# 009_ToSourceBoard.net
KiCad netlist of a schematic drawn in Altium Designer
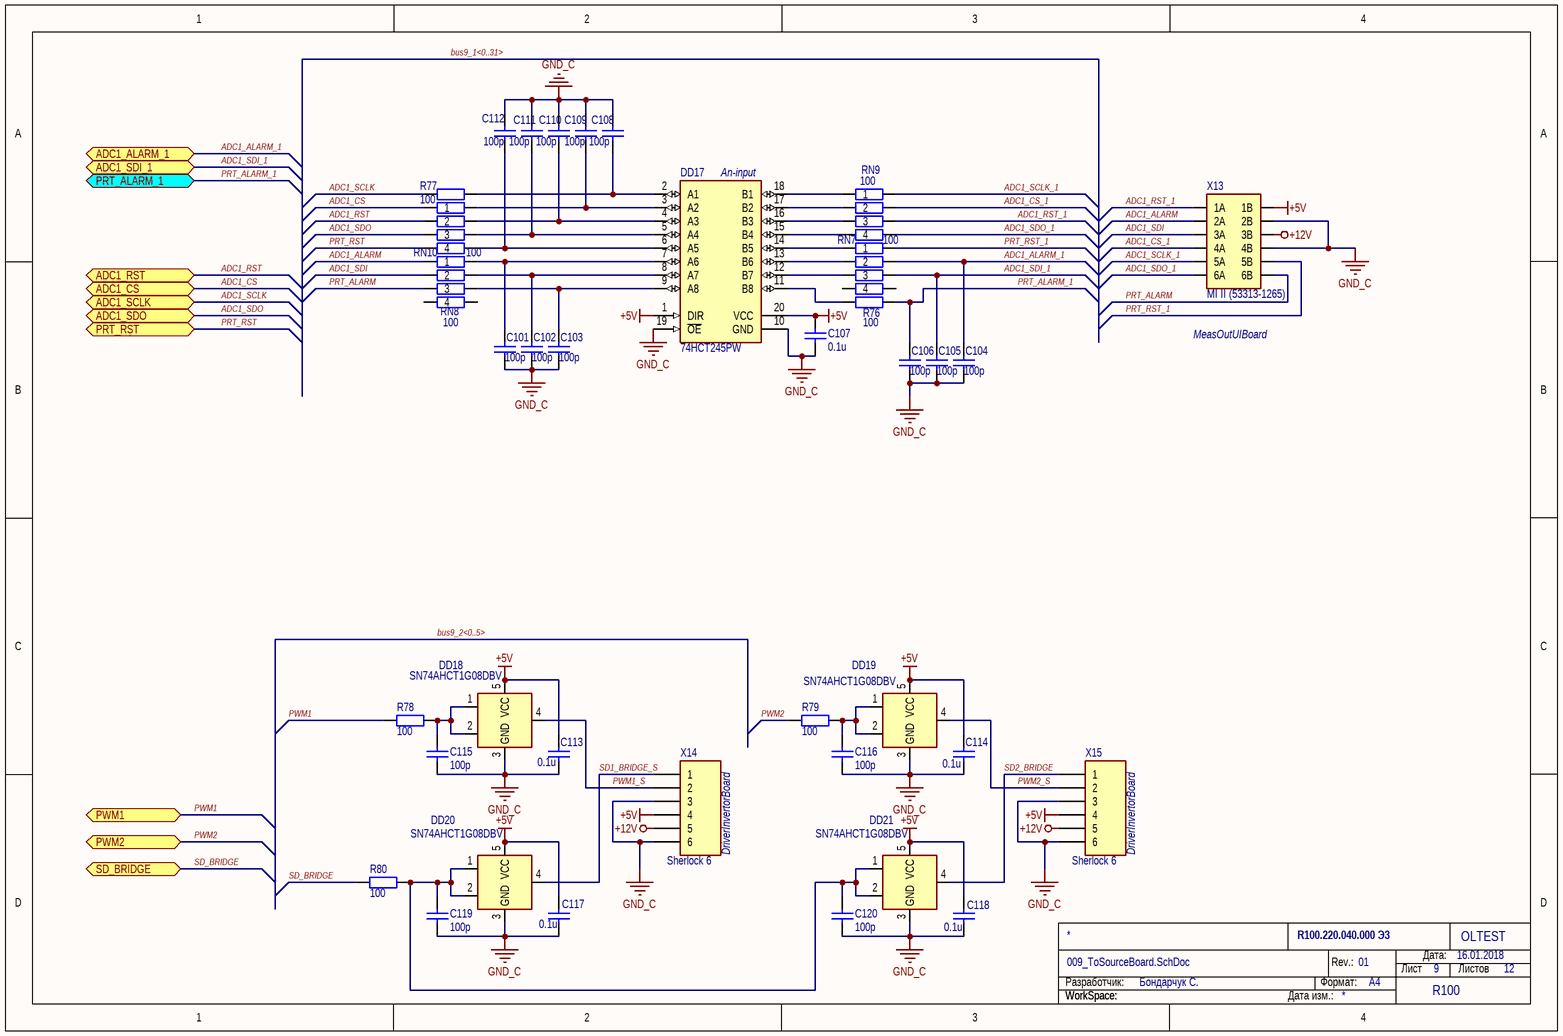
[diagram p0: 009_ToSourceBoard.SchDoc]

(export (version "E")
  (design (tool "Eeschema 10.0.6"))
  (components
    (comp (ref "C101")
      (value "100p")
      (footprint "mainLib:SMD_C_0603")
      (description "SMD C 0603 MURATA 100V 5% NP0")
      (fields (field (name "PARTNUMBER") "GRM1885C2A101JA01") (field (name "MANUFACTURER") "MURATA"))
      (libsource (lib "mainRCLib") (part "C0603 100p 100V 5%"))
    )
    (comp (ref "C102")
      (value "100p")
      (footprint "mainLib:SMD_C_0603")
      (description "SMD C 0603 MURATA 100V 5% NP0")
      (fields (field (name "PARTNUMBER") "GRM1885C2A101JA01") (field (name "MANUFACTURER") "MURATA"))
      (libsource (lib "mainRCLib") (part "C0603 100p 100V 5%"))
    )
    (comp (ref "C103")
      (value "100p")
      (footprint "mainLib:SMD_C_0603")
      (description "SMD C 0603 MURATA 100V 5% NP0")
      (fields (field (name "PARTNUMBER") "GRM1885C2A101JA01") (field (name "MANUFACTURER") "MURATA"))
      (libsource (lib "mainRCLib") (part "C0603 100p 100V 5%"))
    )
    (comp (ref "C104")
      (value "100p")
      (footprint "mainLib:SMD_C_0603")
      (description "SMD C 0603 MURATA 100V 5% NP0")
      (fields (field (name "PARTNUMBER") "GRM1885C2A101JA01") (field (name "MANUFACTURER") "MURATA"))
      (libsource (lib "mainRCLib") (part "C0603 100p 100V 5%"))
    )
    (comp (ref "C105")
      (value "100p")
      (footprint "mainLib:SMD_C_0603")
      (description "SMD C 0603 MURATA 100V 5% NP0")
      (fields (field (name "PARTNUMBER") "GRM1885C2A101JA01") (field (name "MANUFACTURER") "MURATA"))
      (libsource (lib "mainRCLib") (part "C0603 100p 100V 5%"))
    )
    (comp (ref "C106")
      (value "100p")
      (footprint "mainLib:SMD_C_0603")
      (description "SMD C 0603 MURATA 100V 5% NP0")
      (fields (field (name "PARTNUMBER") "GRM1885C2A101JA01") (field (name "MANUFACTURER") "MURATA"))
      (libsource (lib "mainRCLib") (part "C0603 100p 100V 5%"))
    )
    (comp (ref "C107")
      (value "0.1u")
      (footprint "mainLib:SMD_C_0603")
      (description "SMD C 0603 MURATA 50V 10% X7R")
      (fields (field (name "PARTNUMBER") "GRM188R71H104K") (field (name "MANUFACTURER") "MURATA"))
      (libsource (lib "mainRCLib") (part "C0603 0.1u 50V 10%"))
    )
    (comp (ref "C108")
      (value "100p")
      (footprint "mainLib:SMD_C_0603")
      (description "SMD C 0603 MURATA 100V 5% NP0")
      (fields (field (name "PARTNUMBER") "GRM1885C2A101JA01") (field (name "MANUFACTURER") "MURATA"))
      (libsource (lib "mainRCLib") (part "C0603 100p 100V 5%"))
    )
    (comp (ref "C109")
      (value "100p")
      (footprint "mainLib:SMD_C_0603")
      (description "SMD C 0603 MURATA 100V 5% NP0")
      (fields (field (name "PARTNUMBER") "GRM1885C2A101JA01") (field (name "MANUFACTURER") "MURATA"))
      (libsource (lib "mainRCLib") (part "C0603 100p 100V 5%"))
    )
    (comp (ref "C110")
      (value "100p")
      (footprint "mainLib:SMD_C_0603")
      (description "SMD C 0603 MURATA 100V 5% NP0")
      (fields (field (name "PARTNUMBER") "GRM1885C2A101JA01") (field (name "MANUFACTURER") "MURATA"))
      (libsource (lib "mainRCLib") (part "C0603 100p 100V 5%"))
    )
    (comp (ref "C111")
      (value "100p")
      (footprint "mainLib:SMD_C_0603")
      (description "SMD C 0603 MURATA 100V 5% NP0")
      (fields (field (name "PARTNUMBER") "GRM1885C2A101JA01") (field (name "MANUFACTURER") "MURATA"))
      (libsource (lib "mainRCLib") (part "C0603 100p 100V 5%"))
    )
    (comp (ref "C112")
      (value "100p")
      (footprint "mainLib:SMD_C_0603")
      (description "SMD C 0603 MURATA 100V 5% NP0")
      (fields (field (name "PARTNUMBER") "GRM1885C2A101JA01") (field (name "MANUFACTURER") "MURATA"))
      (libsource (lib "mainRCLib") (part "C0603 100p 100V 5%"))
    )
    (comp (ref "C113")
      (value "0.1u")
      (footprint "mainLib:SMD_C_0603")
      (description "SMD C 0603 MURATA 50V 10% X7R")
      (fields (field (name "PARTNUMBER") "GRM188R71H104K") (field (name "MANUFACTURER") "MURATA"))
      (libsource (lib "mainRCLib") (part "C0603 0.1u 50V 10%"))
    )
    (comp (ref "C114")
      (value "0.1u")
      (footprint "mainLib:SMD_C_0603")
      (description "SMD C 0603 MURATA 50V 10% X7R")
      (fields (field (name "PARTNUMBER") "GRM188R71H104K") (field (name "MANUFACTURER") "MURATA"))
      (libsource (lib "mainRCLib") (part "C0603 0.1u 50V 10%"))
    )
    (comp (ref "C115")
      (value "100p")
      (footprint "mainLib:SMD_C_0603")
      (description "SMD C 0603 MURATA 100V 5% NP0")
      (fields (field (name "PARTNUMBER") "GRM1885C2A101JA01") (field (name "MANUFACTURER") "MURATA"))
      (libsource (lib "mainRCLib") (part "C0603 100p 100V 5%"))
    )
    (comp (ref "C116")
      (value "100p")
      (footprint "mainLib:SMD_C_0603")
      (description "SMD C 0603 MURATA 100V 5% NP0")
      (fields (field (name "PARTNUMBER") "GRM1885C2A101JA01") (field (name "MANUFACTURER") "MURATA"))
      (libsource (lib "mainRCLib") (part "C0603 100p 100V 5%"))
    )
    (comp (ref "C117")
      (value "0.1u")
      (footprint "mainLib:SMD_C_0603")
      (description "SMD C 0603 MURATA 50V 10% X7R")
      (fields (field (name "PARTNUMBER") "GRM188R71H104K") (field (name "MANUFACTURER") "MURATA"))
      (libsource (lib "mainRCLib") (part "C0603 0.1u 50V 10%"))
    )
    (comp (ref "C118")
      (value "0.1u")
      (footprint "mainLib:SMD_C_0603")
      (description "SMD C 0603 MURATA 50V 10% X7R")
      (fields (field (name "PARTNUMBER") "GRM188R71H104K") (field (name "MANUFACTURER") "MURATA"))
      (libsource (lib "mainRCLib") (part "C0603 0.1u 50V 10%"))
    )
    (comp (ref "C119")
      (value "100p")
      (footprint "mainLib:SMD_C_0603")
      (description "SMD C 0603 MURATA 100V 5% NP0")
      (fields (field (name "PARTNUMBER") "GRM1885C2A101JA01") (field (name "MANUFACTURER") "MURATA"))
      (libsource (lib "mainRCLib") (part "C0603 100p 100V 5%"))
    )
    (comp (ref "C120")
      (value "100p")
      (footprint "mainLib:SMD_C_0603")
      (description "SMD C 0603 MURATA 100V 5% NP0")
      (fields (field (name "PARTNUMBER") "GRM1885C2A101JA01") (field (name "MANUFACTURER") "MURATA"))
      (libsource (lib "mainRCLib") (part "C0603 100p 100V 5%"))
    )
    (comp (ref "DD17")
      (value "74HCT245PW")
      (footprint "mainLib:PW0020A_M")
      (description "Octal Bus Transceivers With 3-State Outputs, PW0020A")
      (fields (field (name "MANUFACTURER") "NXP"))
      (libsource (lib "mainLib") (part "74HCT245PW"))
    )
    (comp (ref "DD18")
      (value "SN74AHCT1G08DBV")
      (footprint "mainLib:SOT-23(DBV)")
      (description "2-in AND")
      (fields (field (name "MANUFACTURER") "Texas Instruments"))
      (libsource (lib "mainLib") (part "SN74AHCT1G08DBV"))
    )
    (comp (ref "DD19")
      (value "SN74AHCT1G08DBV")
      (footprint "mainLib:SOT-23(DBV)")
      (description "2-in AND")
      (fields (field (name "MANUFACTURER") "Texas Instruments"))
      (libsource (lib "mainLib") (part "SN74AHCT1G08DBV"))
    )
    (comp (ref "DD20")
      (value "SN74AHCT1G08DBV")
      (footprint "mainLib:SOT-23(DBV)")
      (description "2-in AND")
      (fields (field (name "MANUFACTURER") "Texas Instruments"))
      (libsource (lib "mainLib") (part "SN74AHCT1G08DBV"))
    )
    (comp (ref "DD21")
      (value "SN74AHCT1G08DBV")
      (footprint "mainLib:SOT-23(DBV)")
      (description "2-in AND")
      (fields (field (name "MANUFACTURER") "Texas Instruments"))
      (libsource (lib "mainLib") (part "SN74AHCT1G08DBV"))
    )
    (comp (ref "R76")
      (value "100")
      (footprint "SMD_R_0603")
      (description "SMD R 0603 VISHAY 0.1W 75V 1% 100ppm")
      (fields (field (name "PARTNUMBER") "CRCW0603100RFK") (field (name "MANUFACTURER") "VISHAY"))
      (libsource (lib "mainRCLib") (part "R0603 100 1%"))
    )
    (comp (ref "R77")
      (value "100")
      (footprint "SMD_R_0603")
      (description "SMD R 0603 VISHAY 0.1W 75V 1% 100ppm")
      (fields (field (name "PARTNUMBER") "CRCW0603100RFK") (field (name "MANUFACTURER") "VISHAY"))
      (libsource (lib "mainRCLib") (part "R0603 100 1%"))
    )
    (comp (ref "R78")
      (value "100")
      (footprint "SMD_R_0603")
      (description "SMD R 0603 VISHAY 0.1W 75V 1% 100ppm")
      (fields (field (name "PARTNUMBER") "CRCW0603100RFK") (field (name "MANUFACTURER") "VISHAY"))
      (libsource (lib "mainRCLib") (part "R0603 100 1%"))
    )
    (comp (ref "R79")
      (value "100")
      (footprint "SMD_R_0603")
      (description "SMD R 0603 VISHAY 0.1W 75V 1% 100ppm")
      (fields (field (name "PARTNUMBER") "CRCW0603100RFK") (field (name "MANUFACTURER") "VISHAY"))
      (libsource (lib "mainRCLib") (part "R0603 100 1%"))
    )
    (comp (ref "R80")
      (value "100")
      (footprint "SMD_R_0603")
      (description "SMD R 0603 VISHAY 0.1W 75V 1% 100ppm")
      (fields (field (name "PARTNUMBER") "CRCW0603100RFK") (field (name "MANUFACTURER") "VISHAY"))
      (libsource (lib "mainRCLib") (part "R0603 100 1%"))
    )
    (comp (ref "RN7")
      (value "100")
      (footprint "mainLib:CRA06S")
      (description "SMD RESISTOR ARRAY VISHAY 0.063W 50V 1% 100ppm")
      (fields (field (name "PARTNUMBER") "CRA06S083100RF") (field (name "MANUFACTURER") "VISHAY"))
      (libsource (lib "mainRCLib") (part "CRA06S 4x100 1%"))
    )
    (comp (ref "RN8")
      (value "100")
      (footprint "mainLib:CRA06S")
      (description "SMD RESISTOR ARRAY VISHAY 0.063W 50V 1% 100ppm")
      (fields (field (name "PARTNUMBER") "CRA06S083100RF") (field (name "MANUFACTURER") "VISHAY"))
      (libsource (lib "mainRCLib") (part "CRA06S 4x100 1%"))
    )
    (comp (ref "RN9")
      (value "100")
      (footprint "mainLib:CRA06S")
      (description "SMD RESISTOR ARRAY VISHAY 0.063W 50V 1% 100ppm")
      (fields (field (name "PARTNUMBER") "CRA06S083100RF") (field (name "MANUFACTURER") "VISHAY"))
      (libsource (lib "mainRCLib") (part "CRA06S 4x100 1%"))
    )
    (comp (ref "RN10")
      (value "100")
      (footprint "mainLib:CRA06S")
      (description "SMD RESISTOR ARRAY VISHAY 0.063W 50V 1% 100ppm")
      (fields (field (name "PARTNUMBER") "CRA06S083100RF") (field (name "MANUFACTURER") "VISHAY"))
      (libsource (lib "mainRCLib") (part "CRA06S 4x100 1%"))
    )
    (comp (ref "X13")
      (value "MI II (53313-1265)")
      (footprint "mainLib:53313-1265")
      (description "MI II 12 (6x2row), 2A 125V 2mm")
      (fields (field (name "PARTNUMBER") "53313-1265") (field (name "MANUFACTURER") "MOLEX"))
      (libsource (lib "mainLib") (part "53313-1265"))
    )
    (comp (ref "X14")
      (value "Sherlock 6")
      (footprint "mainLib:35362-0650")
      (description "Sherlock 6 Side, 2A 125V 2mm")
      (fields (field (name "PARTNUMBER") "35362-0650") (field (name "MANUFACTURER") "MOLEX"))
      (libsource (lib "mainLib") (part "35363-0650"))
    )
    (comp (ref "X15")
      (value "Sherlock 6")
      (footprint "mainLib:35362-0650")
      (description "Sherlock 6 Side, 2A 125V 2mm")
      (fields (field (name "PARTNUMBER") "35362-0650") (field (name "MANUFACTURER") "MOLEX"))
      (libsource (lib "mainLib") (part "35363-0650"))
    )
  )
  (nets
    (net (code "3") (name "+5V") (class "Default")
      (node (ref "C107") (pin "2") (pinfunction "2_2") (pintype "passive"))
      (node (ref "C113") (pin "2") (pinfunction "2_2") (pintype "passive"))
      (node (ref "C114") (pin "2") (pinfunction "2_2") (pintype "passive"))
      (node (ref "C117") (pin "2") (pinfunction "2_2") (pintype "passive"))
      (node (ref "C118") (pin "2") (pinfunction "2_2") (pintype "passive"))
      (node (ref "DD17") (pin "1") (pinfunction "DIR_1") (pintype "input"))
      (node (ref "DD17") (pin "20") (pinfunction "VCC_20") (pintype "power_in"))
      (node (ref "DD18") (pin "5") (pinfunction "VCC_5") (pintype "passive"))
      (node (ref "DD19") (pin "5") (pinfunction "VCC_5") (pintype "passive"))
      (node (ref "DD20") (pin "5") (pinfunction "VCC_5") (pintype "passive"))
      (node (ref "DD21") (pin "5") (pinfunction "VCC_5") (pintype "passive"))
      (node (ref "X13") (pin "1B") (pinfunction "1B_1B") (pintype "passive"))
      (node (ref "X14") (pin "4") (pinfunction "4_4") (pintype "passive"))
      (node (ref "X15") (pin "4") (pinfunction "4_4") (pintype "passive"))
    )
    (net (code "4") (name "+12V") (class "Default")
      (node (ref "X13") (pin "3B") (pinfunction "3B_3B") (pintype "passive"))
      (node (ref "X14") (pin "5") (pinfunction "5_5") (pintype "passive"))
      (node (ref "X15") (pin "5") (pinfunction "5_5") (pintype "passive"))
    )
    (net (code "5") (name "/ADC1_ALARM") (class "Default")
      (node (ref "RN8") (pin "1") (pinfunction "1_1") (pintype "passive"))
      (node (ref "X13") (pin "2A") (pinfunction "2A_2A") (pintype "passive"))
    )
    (net (code "6") (name "/ADC1_ALARM_1") (class "Default")
      (node (ref "C104") (pin "2") (pinfunction "2_2") (pintype "passive"))
      (node (ref "RN7") (pin "7") (pinfunction "7_7") (pintype "passive"))
    )
    (net (code "7") (name "/ADC1_CS") (class "Default")
      (node (ref "RN10") (pin "1") (pinfunction "1_1") (pintype "passive"))
    )
    (net (code "8") (name "/ADC1_CS_1") (class "Default")
      (node (ref "RN9") (pin "7") (pinfunction "7_7") (pintype "passive"))
      (node (ref "X13") (pin "4A") (pinfunction "4A_4A") (pintype "passive"))
    )
    (net (code "9") (name "/ADC1_RST") (class "Default")
      (node (ref "RN10") (pin "2") (pinfunction "2_2") (pintype "passive"))
    )
    (net (code "10") (name "/ADC1_RST_1") (class "Default")
      (node (ref "RN9") (pin "6") (pinfunction "6_6") (pintype "passive"))
      (node (ref "X13") (pin "1A") (pinfunction "1A_1A") (pintype "passive"))
    )
    (net (code "11") (name "/ADC1_SCLK") (class "Default")
      (node (ref "R77") (pin "1") (pinfunction "1_1") (pintype "passive"))
    )
    (net (code "12") (name "/ADC1_SCLK_1") (class "Default")
      (node (ref "RN9") (pin "8") (pinfunction "8_8") (pintype "passive"))
      (node (ref "X13") (pin "5A") (pinfunction "5A_5A") (pintype "passive"))
    )
    (net (code "13") (name "/ADC1_SDI") (class "Default")
      (node (ref "RN8") (pin "2") (pinfunction "2_2") (pintype "passive"))
      (node (ref "X13") (pin "3A") (pinfunction "3A_3A") (pintype "passive"))
    )
    (net (code "14") (name "/ADC1_SDI_1") (class "Default")
      (node (ref "C105") (pin "2") (pinfunction "2_2") (pintype "passive"))
      (node (ref "RN7") (pin "6") (pinfunction "6_6") (pintype "passive"))
    )
    (net (code "15") (name "/ADC1_SDO") (class "Default")
      (node (ref "RN10") (pin "3") (pinfunction "3_3") (pintype "passive"))
    )
    (net (code "16") (name "/ADC1_SDO_1") (class "Default")
      (node (ref "RN9") (pin "5") (pinfunction "5_5") (pintype "passive"))
      (node (ref "X13") (pin "6A") (pinfunction "6A_6A") (pintype "passive"))
    )
    (net (code "17") (name "/PRT_ALARM") (class "Default")
      (node (ref "RN8") (pin "3") (pinfunction "3_3") (pintype "passive"))
      (node (ref "X13") (pin "6B") (pinfunction "6B_6B") (pintype "passive"))
    )
    (net (code "18") (name "/PRT_ALARM_1") (class "Default")
      (node (ref "C106") (pin "2") (pinfunction "2_2") (pintype "passive"))
      (node (ref "R76") (pin "2") (pinfunction "2_2") (pintype "passive"))
    )
    (net (code "19") (name "/PRT_RST") (class "Default")
      (node (ref "RN10") (pin "4") (pinfunction "4_4") (pintype "passive"))
    )
    (net (code "20") (name "/PRT_RST_1") (class "Default")
      (node (ref "RN7") (pin "8") (pinfunction "8_8") (pintype "passive"))
      (node (ref "X13") (pin "5B") (pinfunction "5B_5B") (pintype "passive"))
    )
    (net (code "21") (name "/PWM1") (class "Default")
      (node (ref "R78") (pin "1") (pinfunction "1_1") (pintype "passive"))
    )
    (net (code "22") (name "/PWM1_S") (class "Default")
      (node (ref "DD18") (pin "4") (pintype "passive"))
      (node (ref "X14") (pin "2") (pinfunction "2_2") (pintype "passive"))
    )
    (net (code "23") (name "/PWM2") (class "Default")
      (node (ref "R79") (pin "1") (pinfunction "1_1") (pintype "passive"))
    )
    (net (code "24") (name "/PWM2_S") (class "Default")
      (node (ref "DD19") (pin "4") (pintype "passive"))
      (node (ref "X15") (pin "2") (pinfunction "2_2") (pintype "passive"))
    )
    (net (code "25") (name "/SD1_BRIDGE_S") (class "Default")
      (node (ref "DD20") (pin "4") (pintype "passive"))
      (node (ref "X14") (pin "1") (pinfunction "1_1") (pintype "passive"))
    )
    (net (code "26") (name "/SD2_BRIDGE") (class "Default")
      (node (ref "DD21") (pin "4") (pintype "passive"))
      (node (ref "X15") (pin "1") (pinfunction "1_1") (pintype "passive"))
    )
    (net (code "27") (name "/SD_BRIDGE") (class "Default")
      (node (ref "R80") (pin "1") (pinfunction "1_1") (pintype "passive"))
    )
    (net (code "30") (name "GND_C") (class "Default")
      (node (ref "C101") (pin "1") (pinfunction "1_1") (pintype "passive"))
      (node (ref "C102") (pin "1") (pinfunction "1_1") (pintype "passive"))
      (node (ref "C103") (pin "1") (pinfunction "1_1") (pintype "passive"))
      (node (ref "C104") (pin "1") (pinfunction "1_1") (pintype "passive"))
      (node (ref "C105") (pin "1") (pinfunction "1_1") (pintype "passive"))
      (node (ref "C106") (pin "1") (pinfunction "1_1") (pintype "passive"))
      (node (ref "C107") (pin "1") (pinfunction "1_1") (pintype "passive"))
      (node (ref "C108") (pin "1") (pinfunction "1_1") (pintype "passive"))
      (node (ref "C109") (pin "1") (pinfunction "1_1") (pintype "passive"))
      (node (ref "C110") (pin "1") (pinfunction "1_1") (pintype "passive"))
      (node (ref "C111") (pin "1") (pinfunction "1_1") (pintype "passive"))
      (node (ref "C112") (pin "1") (pinfunction "1_1") (pintype "passive"))
      (node (ref "C113") (pin "1") (pinfunction "1_1") (pintype "passive"))
      (node (ref "C114") (pin "1") (pinfunction "1_1") (pintype "passive"))
      (node (ref "C115") (pin "1") (pinfunction "1_1") (pintype "passive"))
      (node (ref "C116") (pin "1") (pinfunction "1_1") (pintype "passive"))
      (node (ref "C117") (pin "1") (pinfunction "1_1") (pintype "passive"))
      (node (ref "C118") (pin "1") (pinfunction "1_1") (pintype "passive"))
      (node (ref "C119") (pin "1") (pinfunction "1_1") (pintype "passive"))
      (node (ref "C120") (pin "1") (pinfunction "1_1") (pintype "passive"))
      (node (ref "DD17") (pin "10") (pinfunction "GND_10") (pintype "power_in"))
      (node (ref "DD17") (pin "19") (pinfunction "~{OE}_19") (pintype "input"))
      (node (ref "DD18") (pin "3") (pinfunction "GND_3") (pintype "passive"))
      (node (ref "DD19") (pin "3") (pinfunction "GND_3") (pintype "passive"))
      (node (ref "DD20") (pin "3") (pinfunction "GND_3") (pintype "passive"))
      (node (ref "DD21") (pin "3") (pinfunction "GND_3") (pintype "passive"))
      (node (ref "X13") (pin "2B") (pinfunction "2B_2B") (pintype "passive"))
      (node (ref "X13") (pin "4B") (pinfunction "4B_4B") (pintype "passive"))
      (node (ref "X14") (pin "3") (pinfunction "3_3") (pintype "passive"))
      (node (ref "X14") (pin "6") (pinfunction "6_6") (pintype "passive"))
      (node (ref "X15") (pin "3") (pinfunction "3_3") (pintype "passive"))
      (node (ref "X15") (pin "6") (pinfunction "6_6") (pintype "passive"))
    )
    (net (code "31") (name "Net-(C115-Pad2)") (class "Default")
      (node (ref "C115") (pin "2") (pinfunction "2_2") (pintype "passive"))
      (node (ref "DD18") (pin "1") (pintype "passive"))
      (node (ref "DD18") (pin "2") (pintype "passive"))
      (node (ref "R78") (pin "2") (pinfunction "2_2") (pintype "passive"))
    )
    (net (code "32") (name "Net-(C116-Pad2)") (class "Default")
      (node (ref "C116") (pin "2") (pinfunction "2_2") (pintype "passive"))
      (node (ref "DD19") (pin "1") (pintype "passive"))
      (node (ref "DD19") (pin "2") (pintype "passive"))
      (node (ref "R79") (pin "2") (pinfunction "2_2") (pintype "passive"))
    )
    (net (code "33") (name "Net-(C119-Pad2)") (class "Default")
      (node (ref "C119") (pin "2") (pinfunction "2_2") (pintype "passive"))
      (node (ref "C120") (pin "2") (pinfunction "2_2") (pintype "passive"))
      (node (ref "DD20") (pin "1") (pintype "passive"))
      (node (ref "DD20") (pin "2") (pintype "passive"))
      (node (ref "DD21") (pin "1") (pintype "passive"))
      (node (ref "DD21") (pin "2") (pintype "passive"))
      (node (ref "R80") (pin "2") (pinfunction "2_2") (pintype "passive"))
    )
    (net (code "34") (name "Net-(DD17-A1)") (class "Default")
      (node (ref "C108") (pin "2") (pinfunction "2_2") (pintype "passive"))
      (node (ref "DD17") (pin "2") (pinfunction "A1_2") (pintype "bidirectional"))
      (node (ref "R77") (pin "2") (pinfunction "2_2") (pintype "passive"))
    )
    (net (code "35") (name "Net-(DD17-A2)") (class "Default")
      (node (ref "C109") (pin "2") (pinfunction "2_2") (pintype "passive"))
      (node (ref "DD17") (pin "3") (pinfunction "A2_3") (pintype "bidirectional"))
      (node (ref "RN10") (pin "8") (pinfunction "8_8") (pintype "passive"))
    )
    (net (code "36") (name "Net-(DD17-A3)") (class "Default")
      (node (ref "C110") (pin "2") (pinfunction "2_2") (pintype "passive"))
      (node (ref "DD17") (pin "4") (pinfunction "A3_4") (pintype "bidirectional"))
      (node (ref "RN10") (pin "7") (pinfunction "7_7") (pintype "passive"))
    )
    (net (code "37") (name "Net-(DD17-A4)") (class "Default")
      (node (ref "C111") (pin "2") (pinfunction "2_2") (pintype "passive"))
      (node (ref "DD17") (pin "5") (pinfunction "A4_5") (pintype "bidirectional"))
      (node (ref "RN10") (pin "6") (pinfunction "6_6") (pintype "passive"))
    )
    (net (code "38") (name "Net-(DD17-A5)") (class "Default")
      (node (ref "C112") (pin "2") (pinfunction "2_2") (pintype "passive"))
      (node (ref "DD17") (pin "6") (pinfunction "A5_6") (pintype "bidirectional"))
      (node (ref "RN10") (pin "5") (pinfunction "5_5") (pintype "passive"))
    )
    (net (code "39") (name "Net-(DD17-A6)") (class "Default")
      (node (ref "C101") (pin "2") (pinfunction "2_2") (pintype "passive"))
      (node (ref "DD17") (pin "7") (pinfunction "A6_7") (pintype "bidirectional"))
      (node (ref "RN8") (pin "8") (pinfunction "8_8") (pintype "passive"))
    )
    (net (code "40") (name "Net-(DD17-A7)") (class "Default")
      (node (ref "C102") (pin "2") (pinfunction "2_2") (pintype "passive"))
      (node (ref "DD17") (pin "8") (pinfunction "A7_8") (pintype "bidirectional"))
      (node (ref "RN8") (pin "7") (pinfunction "7_7") (pintype "passive"))
    )
    (net (code "41") (name "Net-(DD17-A8)") (class "Default")
      (node (ref "C103") (pin "2") (pinfunction "2_2") (pintype "passive"))
      (node (ref "DD17") (pin "9") (pinfunction "A8_9") (pintype "bidirectional"))
      (node (ref "RN8") (pin "6") (pinfunction "6_6") (pintype "passive"))
    )
    (net (code "42") (name "Net-(DD17-B1)") (class "Default")
      (node (ref "DD17") (pin "18") (pinfunction "B1_18") (pintype "bidirectional"))
      (node (ref "RN9") (pin "1") (pinfunction "1_1") (pintype "passive"))
    )
    (net (code "43") (name "Net-(DD17-B2)") (class "Default")
      (node (ref "DD17") (pin "17") (pinfunction "B2_17") (pintype "bidirectional"))
      (node (ref "RN9") (pin "2") (pinfunction "2_2") (pintype "passive"))
    )
    (net (code "44") (name "Net-(DD17-B3)") (class "Default")
      (node (ref "DD17") (pin "16") (pinfunction "B3_16") (pintype "bidirectional"))
      (node (ref "RN9") (pin "3") (pinfunction "3_3") (pintype "passive"))
    )
    (net (code "45") (name "Net-(DD17-B4)") (class "Default")
      (node (ref "DD17") (pin "15") (pinfunction "B4_15") (pintype "bidirectional"))
      (node (ref "RN9") (pin "4") (pinfunction "4_4") (pintype "passive"))
    )
    (net (code "46") (name "Net-(DD17-B5)") (class "Default")
      (node (ref "DD17") (pin "14") (pinfunction "B5_14") (pintype "bidirectional"))
      (node (ref "RN7") (pin "1") (pinfunction "1_1") (pintype "passive"))
    )
    (net (code "47") (name "Net-(DD17-B6)") (class "Default")
      (node (ref "DD17") (pin "13") (pinfunction "B6_13") (pintype "bidirectional"))
      (node (ref "RN7") (pin "2") (pinfunction "2_2") (pintype "passive"))
    )
    (net (code "48") (name "Net-(DD17-B7)") (class "Default")
      (node (ref "DD17") (pin "12") (pinfunction "B7_12") (pintype "bidirectional"))
      (node (ref "RN7") (pin "3") (pinfunction "3_3") (pintype "passive"))
    )
    (net (code "49") (name "Net-(DD17-B8)") (class "Default")
      (node (ref "DD17") (pin "11") (pinfunction "B8_11") (pintype "bidirectional"))
      (node (ref "R76") (pin "1") (pinfunction "1_1") (pintype "passive"))
    )
    (net (code "50") (name "unconnected-(RN7-Pad4)") (class "Default")
      (node (ref "RN7") (pin "4") (pinfunction "4_4") (pintype "passive"))
    )
    (net (code "51") (name "unconnected-(RN7-Pad5)") (class "Default")
      (node (ref "RN7") (pin "5") (pinfunction "5_5") (pintype "passive"))
    )
    (net (code "52") (name "unconnected-(RN8-Pad4)") (class "Default")
      (node (ref "RN8") (pin "4") (pinfunction "4_4") (pintype "passive"))
    )
    (net (code "53") (name "unconnected-(RN8-Pad5)") (class "Default")
      (node (ref "RN8") (pin "5") (pinfunction "5_5") (pintype "passive"))
    )
  )
)
